# rf_spectrum.net
KiCad netlist of a schematic drawn in EAGLE
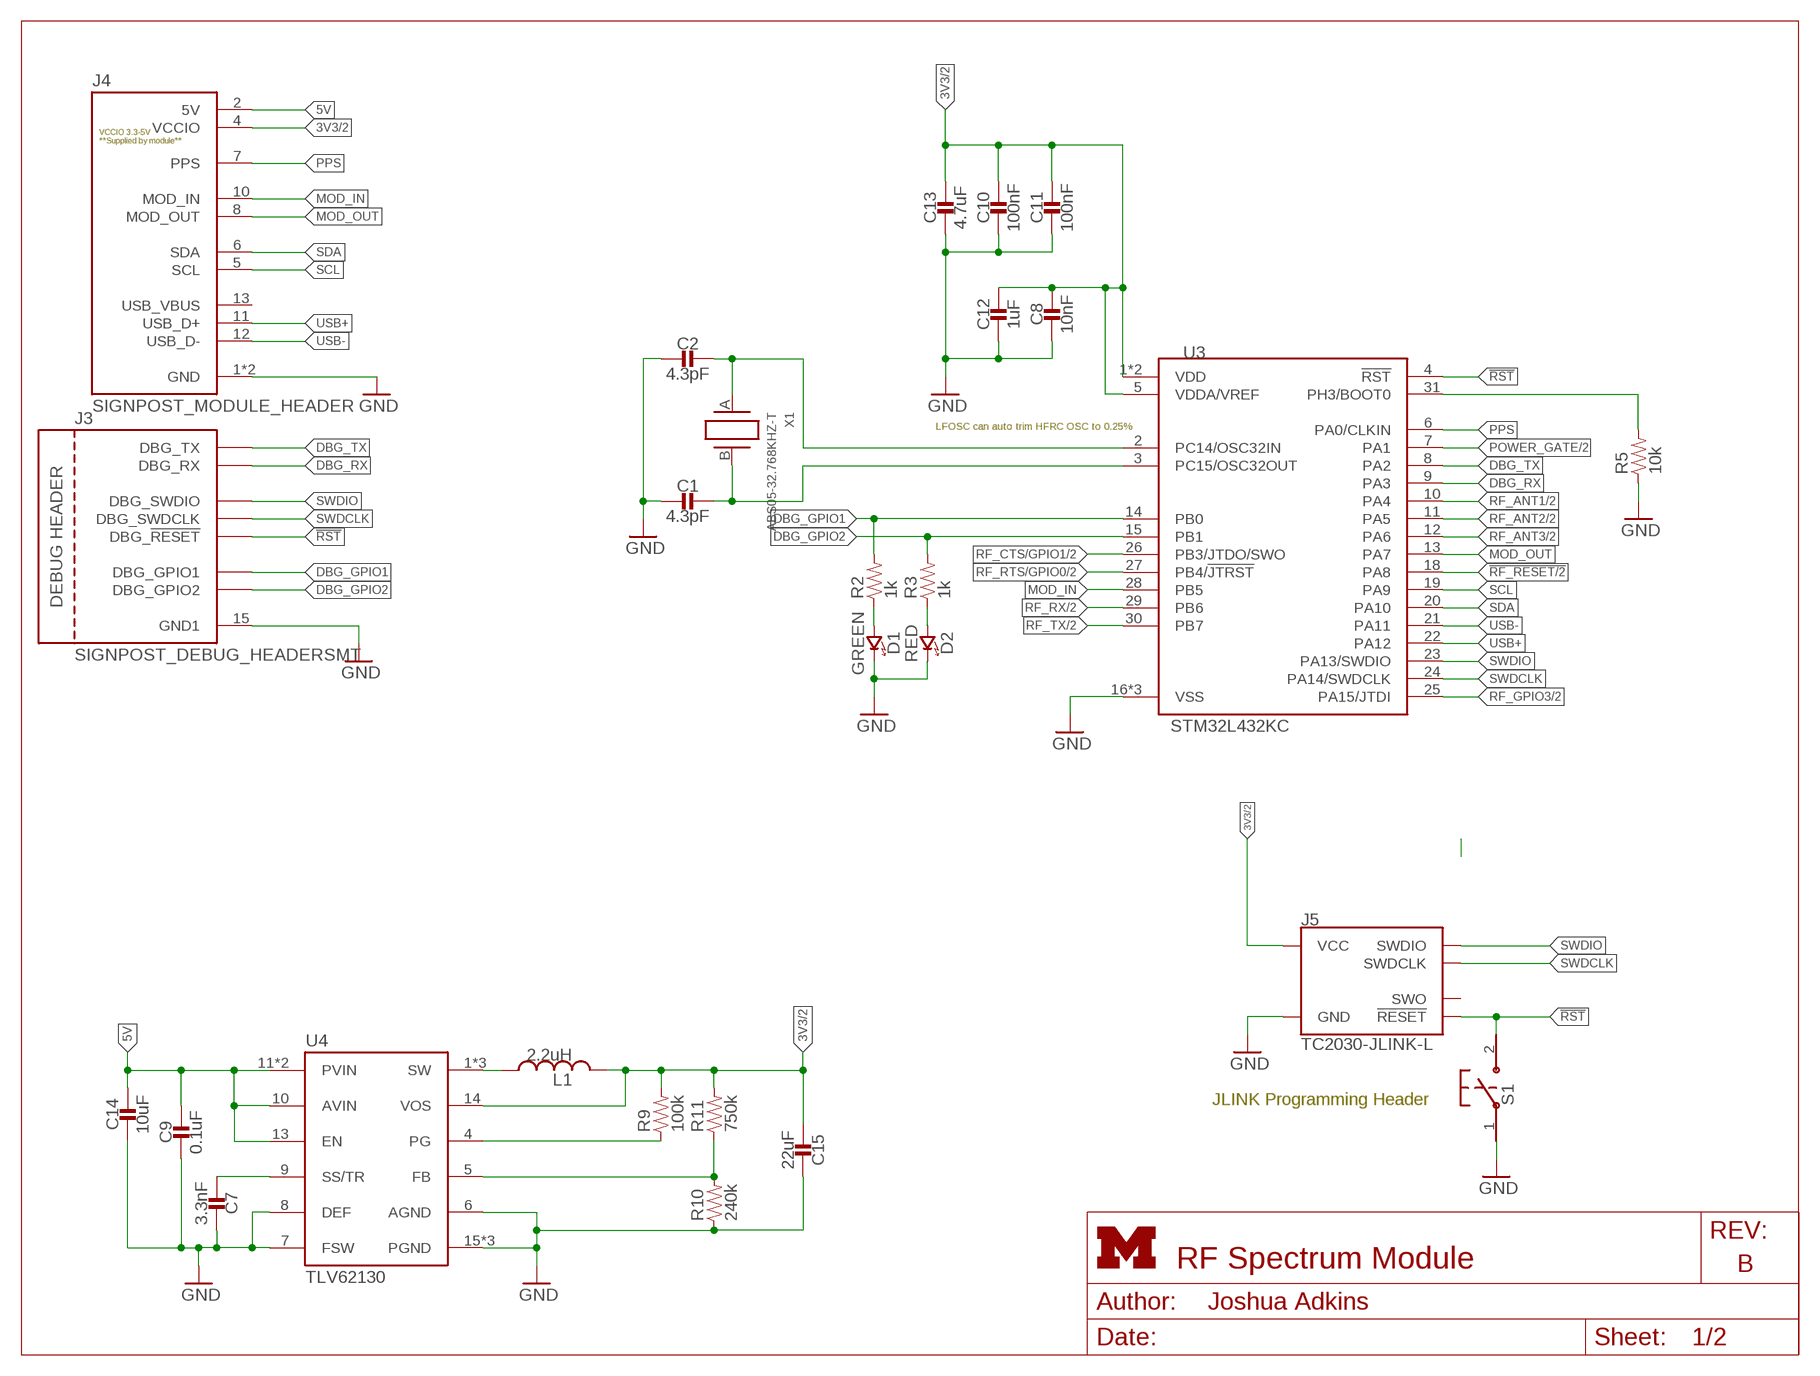
[diagram p0: schematic, sheet 1]
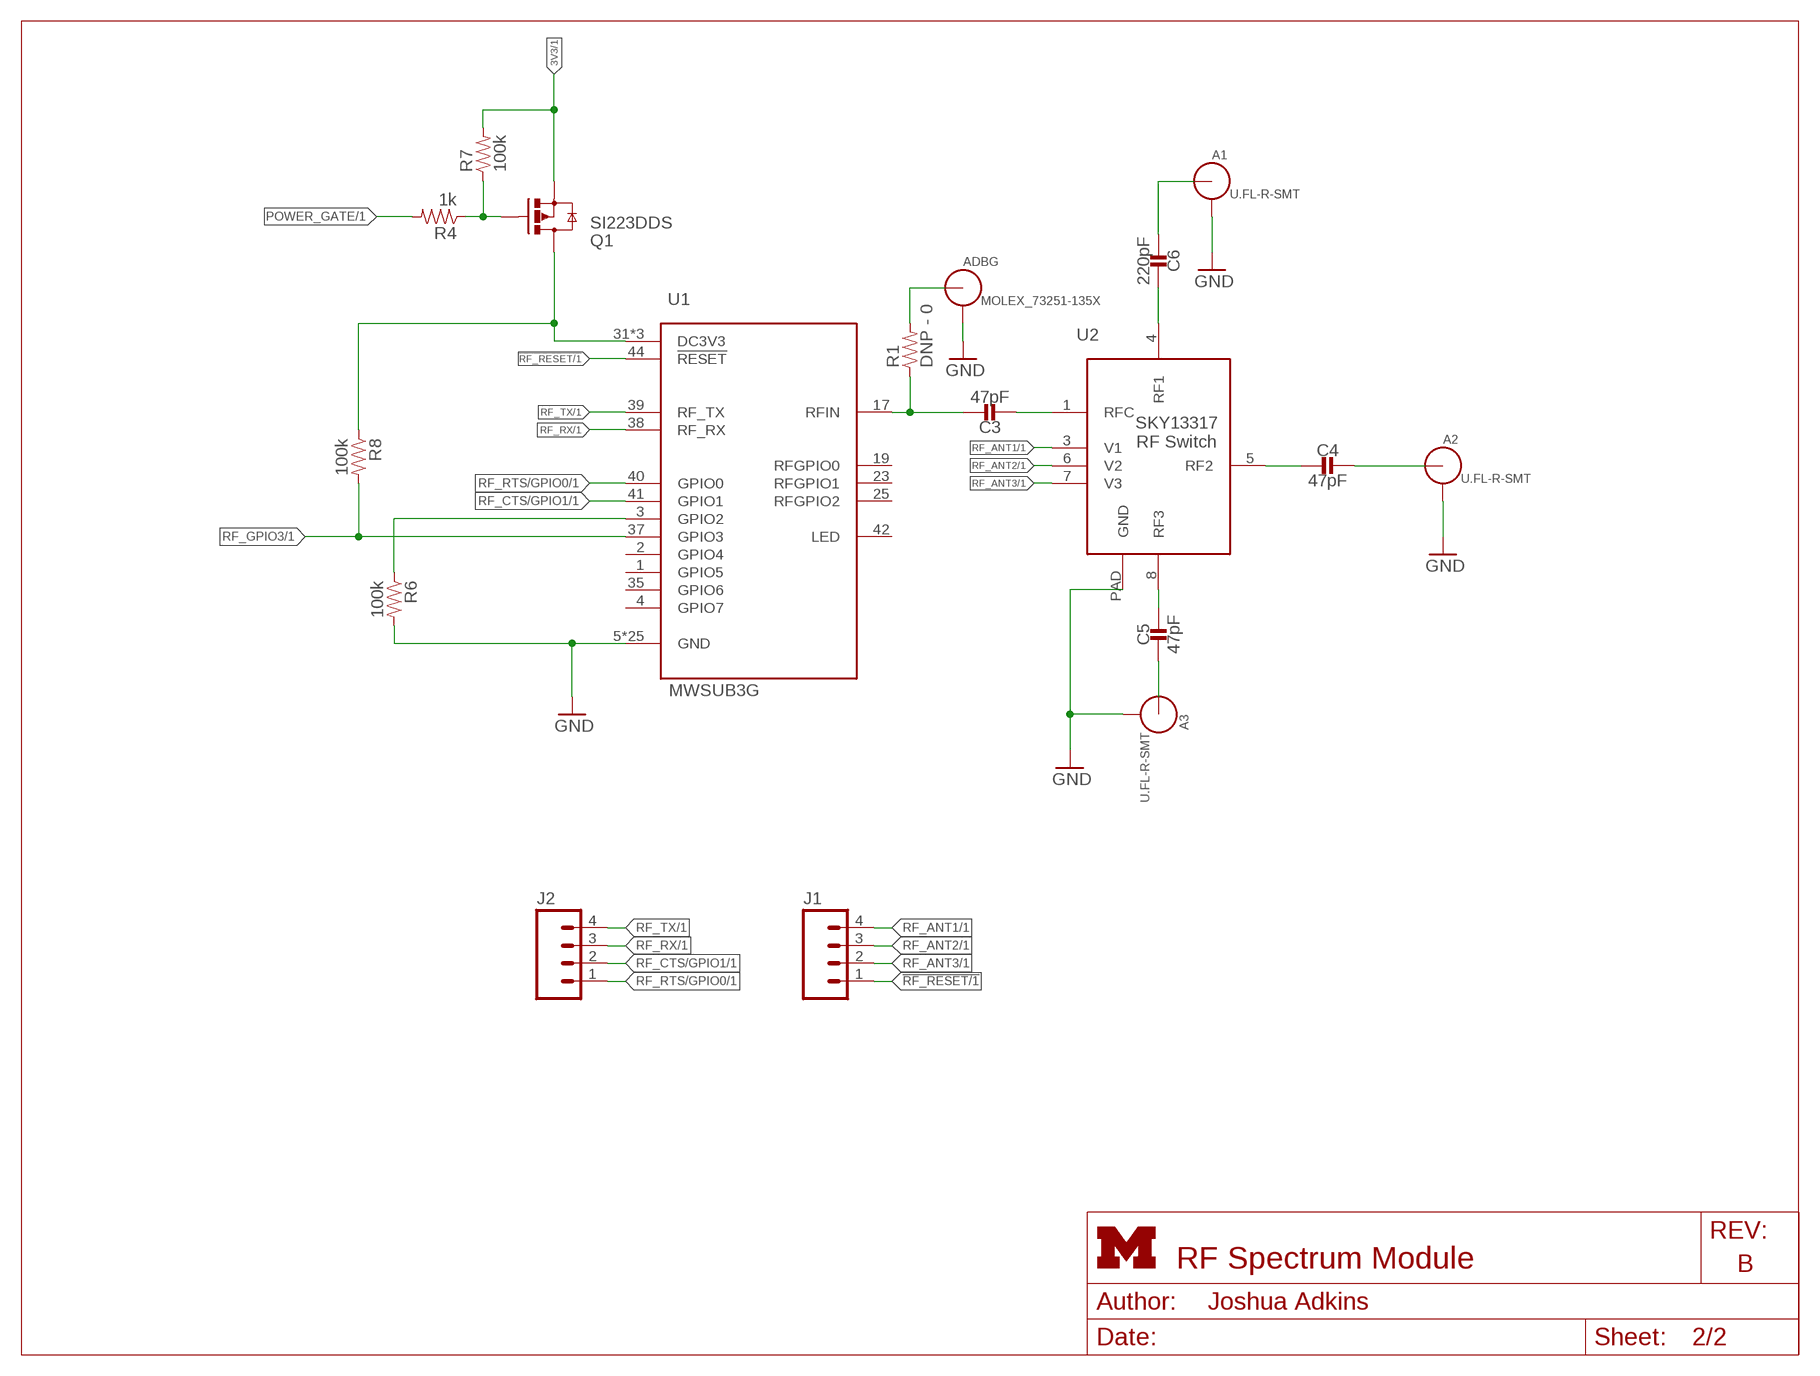
[diagram p1: schematic, sheet 2]

(export (version "E")
  (design (tool "Eeschema 10.0.6"))
  (components
    (comp (ref "C1")
      (value "4.3pF")
      (footprint "eagle-import:0402_CAP")
      (fields (field (name "MANUFACTURER") "Murata") (field (name "MPN") "GRM1555C1H4R3BA01D"))
      (libsource (lib "eagle-import") (part "CAPACITOR0402_CAP"))
    )
    (comp (ref "C2")
      (value "4.3pF")
      (footprint "eagle-import:0402_CAP")
      (fields (field (name "MANUFACTURER") "Murata") (field (name "MPN") "GRM1555C1H4R3BA01D"))
      (libsource (lib "eagle-import") (part "CAPACITOR0402_CAP"))
    )
    (comp (ref "C7")
      (value "3.3nF")
      (footprint "eagle-import:0603_CAP")
      (fields (field (name "MANUFACTURER") "Murata") (field (name "MPN") "GRM188R71H332KA01D"))
      (libsource (lib "eagle-import") (part "CAPACITOR0603_CAP"))
    )
    (comp (ref "C8")
      (value "10nF")
      (footprint "eagle-import:0402_CAP")
      (fields (field (name "MANUFACTURER") "Murata") (field (name "MPN") "GRM155R71H103KA88D"))
      (libsource (lib "eagle-import") (part "CAPACITOR0402_CAP"))
    )
    (comp (ref "C9")
      (value "0.1uF")
      (footprint "eagle-import:0603_CAP")
      (fields (field (name "MANUFACTURER") "Murata") (field (name "MPN") "GRM188R71C104KA01D"))
      (libsource (lib "eagle-import") (part "CAPACITOR0603_CAP"))
    )
    (comp (ref "C10")
      (value "100nF")
      (footprint "eagle-import:0402_CAP")
      (fields (field (name "MANUFACTURER") "Murata") (field (name "MPN") "GRM155R71C104KA88J"))
      (libsource (lib "eagle-import") (part "CAPACITOR0402_CAP"))
    )
    (comp (ref "C11")
      (value "100nF")
      (footprint "eagle-import:0402_CAP")
      (fields (field (name "MANUFACTURER") "Murata") (field (name "MPN") "GRM155R71C104KA88J"))
      (libsource (lib "eagle-import") (part "CAPACITOR0402_CAP"))
    )
    (comp (ref "C12")
      (value "1uF")
      (footprint "eagle-import:0402_CAP")
      (fields (field (name "MANUFACTURER") "Murata") (field (name "MPN") "GRM155R60J105KE19D"))
      (libsource (lib "eagle-import") (part "CAPACITOR0402_CAP"))
    )
    (comp (ref "C13")
      (value "4.7uF")
      (footprint "eagle-import:0402_CAP")
      (fields (field (name "MANUFACTURER") "Murata") (field (name "MPN") "GRM155R60J475ME47D"))
      (libsource (lib "eagle-import") (part "CAPACITOR0402_CAP"))
    )
    (comp (ref "C14")
      (value "10uF")
      (footprint "eagle-import:0603_CAP")
      (fields (field (name "MANUFACTURER") "Murata") (field (name "MPN") "GRM188R60J106ME47J"))
      (libsource (lib "eagle-import") (part "CAPACITOR0603_CAP"))
    )
    (comp (ref "C15")
      (value "22uF")
      (footprint "eagle-import:0603_CAP")
      (fields (field (name "MANUFACTURER") "Murata") (field (name "MPN") "GRM188R60J226MEA0D"))
      (libsource (lib "eagle-import") (part "CAPACITOR0603_CAP"))
    )
    (comp (ref "D1")
      (value "GREEN")
      (footprint "eagle-import:LED-0603")
      (fields (field (name "MANUFACTURER") "Lite-ON") (field (name "MPN") "LTST-C191KGKT"))
      (libsource (lib "eagle-import") (part "LED0603"))
    )
    (comp (ref "D2")
      (value "RED")
      (footprint "eagle-import:LED-0603")
      (fields (field (name "MANUFACTURER") "Lite-On") (field (name "MPN") "LTST-C191KRKT"))
      (libsource (lib "eagle-import") (part "LED0603"))
    )
    (comp (ref "J3")
      (value "SIGNPOST_DEBUG_HEADERSMT")
      (footprint "eagle-import:SIGNPOST_DEBUG_HEADER_SMT")
      (fields (field (name "MANUFACTURER") "Molex") (field (name "MPN") "0015912080"))
      (libsource (lib "eagle-import") (part "SIGNPOST_DEBUG_HEADERSMT"))
    )
    (comp (ref "J4")
      (value "SIGNPOST_MODULE_HEADER")
      (footprint "eagle-import:SIGNPOST_MODULE_HEADER")
      (fields (field (name "MANUFACTURER") "Sullins Connector") (field (name "MPN") "SBH11-PBPC-D07-ST-BK"))
      (libsource (lib "eagle-import") (part "SIGNPOST_MODULE_HEADER"))
    )
    (comp (ref "J5")
      (value "TC2030-JLINK-L")
      (footprint "eagle-import:TC2030-IDC")
      (libsource (lib "eagle-import") (part "TC2030-JLINK-L"))
    )
    (comp (ref "L1")
      (value "2.2uH")
      (footprint "eagle-import:IHL-1212BZ-11")
      (fields (field (name "MANUFACTURER") "Vishay Dale") (field (name "MPN") "IHLP1212BZER2R2M11"))
      (libsource (lib "eagle-import") (part "INDUCTORIHL"))
    )
    (comp (ref "R2")
      (value "1k")
      (footprint "eagle-import:0402_RES")
      (fields (field (name "MANUFACTURER") "Yageo") (field (name "MPN") "RC0402JR-071KL"))
      (libsource (lib "eagle-import") (part "RESISTOR0402_RES"))
    )
    (comp (ref "R3")
      (value "1k")
      (footprint "eagle-import:0402_RES")
      (fields (field (name "MANUFACTURER") "Yageo") (field (name "MPN") "RC0402JR-071KL"))
      (libsource (lib "eagle-import") (part "RESISTOR0402_RES"))
    )
    (comp (ref "R5")
      (value "10k")
      (footprint "eagle-import:0402_RES")
      (fields (field (name "MANUFACTURER") "Yageo") (field (name "MPN") "RC0402JR-071KL"))
      (libsource (lib "eagle-import") (part "RESISTOR0402_RES"))
    )
    (comp (ref "R9")
      (value "100k")
      (footprint "eagle-import:0603-RES")
      (fields (field (name "MANUFACTURER") "Yageo") (field (name "MPN") "RC0603JR-07100KL"))
      (libsource (lib "eagle-import") (part "RESISTOR0603_RES"))
    )
    (comp (ref "R10")
      (value "240k")
      (footprint "eagle-import:0603-RES")
      (fields (field (name "MANUFACTURER") "Yageo") (field (name "MPN") "RC0603JR-07240KL"))
      (libsource (lib "eagle-import") (part "RESISTOR0603_RES"))
    )
    (comp (ref "R11")
      (value "750k")
      (footprint "eagle-import:0603-RES")
      (fields (field (name "MANUFACTURER") "Yageo") (field (name "MPN") "311-750KGRCT-ND"))
      (libsource (lib "eagle-import") (part "RESISTOR0603_RES"))
    )
    (comp (ref "S1")
      (value "B3U-1000P")
      (footprint "eagle-import:B3U-1000P")
      (fields (field (name "MANUFACTURER") "Omron"))
      (libsource (lib "eagle-import") (part "B3U-1000P"))
    )
    (comp (ref "U3")
      (value "STM32L432KC")
      (footprint "eagle-import:UQFN-32")
      (fields (field (name "MANUFACTURER") "STMicroelectronics") (field (name "MPN") "STM32L432KCU6"))
      (libsource (lib "eagle-import") (part "STM32L432KC"))
    )
    (comp (ref "U4")
      (value "TLV62130")
      (footprint "eagle-import:TQFN-16_3MM")
      (fields (field (name "MANUFACTURER") "Texas Instruments") (field (name "MPN") "TLV62130RGTR"))
      (libsource (lib "eagle-import") (part "TLV62130"))
    )
    (comp (ref "X1")
      (value "ABS05-32.768KHZ-T")
      (footprint "eagle-import:ABS05")
      (fields (field (name "MANUFACTURER") "Abracon"))
      (libsource (lib "eagle-import") (part "ABS05-32.768KHZ-T"))
    )
    (comp (ref "A1")
      (value "U.FL-R-SMT")
      (footprint "eagle-import:U.FL_SMT")
      (fields (field (name "MANUFACTURER") "Hirose") (field (name "MPN") "U.FL-R-SMT-1(01)"))
      (libsource (lib "eagle-import") (part "U.FL-R-SMT"))
    )
    (comp (ref "A2")
      (value "U.FL-R-SMT")
      (footprint "eagle-import:U.FL_SMT")
      (fields (field (name "MANUFACTURER") "Hirose") (field (name "MPN") "U.FL-R-SMT-1(01)"))
      (libsource (lib "eagle-import") (part "U.FL-R-SMT"))
    )
    (comp (ref "A3")
      (value "U.FL-R-SMT")
      (footprint "eagle-import:U.FL_SMT")
      (fields (field (name "MANUFACTURER") "Hirose") (field (name "MPN") "U.FL-R-SMT-1(01)"))
      (libsource (lib "eagle-import") (part "U.FL-R-SMT"))
    )
    (comp (ref "ADBG")
      (value "MOLEX_73251-135X")
      (footprint "eagle-import:SMA-J_PCB")
      (fields (field (name "MANUFACTURER") "Molex") (field (name "MPN") "0732511350"))
      (libsource (lib "eagle-import") (part "MOLEX_73251-135X"))
    )
    (comp (ref "C3")
      (value "47pF")
      (footprint "eagle-import:0402_CAP")
      (fields (field (name "MANUFACTURER") "Murata") (field (name "MPN") "GRM1555C1H470FA01D"))
      (libsource (lib "eagle-import") (part "CAPACITOR0402_CAP"))
    )
    (comp (ref "C4")
      (value "47pF")
      (footprint "eagle-import:0402_CAP")
      (fields (field (name "MANUFACTURER") "Murata") (field (name "MPN") "GRM1555C1H470FA01D"))
      (libsource (lib "eagle-import") (part "CAPACITOR0402_CAP"))
    )
    (comp (ref "C5")
      (value "47pF")
      (footprint "eagle-import:0402_CAP")
      (fields (field (name "MANUFACTURER") "Murata") (field (name "MPN") "GRM1555C1H470FA01D"))
      (libsource (lib "eagle-import") (part "CAPACITOR0402_CAP"))
    )
    (comp (ref "C6")
      (value "220pF")
      (footprint "eagle-import:0402_CAP")
      (fields (field (name "MANUFACTURER") "Murata") (field (name "MPN") "GRM1555C1H221JA01D"))
      (libsource (lib "eagle-import") (part "CAPACITOR0402_CAP"))
    )
    (comp (ref "J1")
      (value "M04PTH")
      (footprint "eagle-import:1X04")
      (fields (field (name "MANUFACTURER") "Molex") (field (name "MPN") "0901200764"))
      (libsource (lib "eagle-import") (part "M04PTH"))
    )
    (comp (ref "J2")
      (value "M04PTH")
      (footprint "eagle-import:1X04")
      (fields (field (name "MANUFACTURER") "Molex") (field (name "MPN") "0901200764"))
      (libsource (lib "eagle-import") (part "M04PTH"))
    )
    (comp (ref "Q1")
      (value "SI223DDS")
      (footprint "eagle-import:SOT23-3")
      (fields (field (name "MANUFACTURER") "Vishay Siliconix") (field (name "MPN") "SI2333DDS-T1-GE3"))
      (libsource (lib "eagle-import") (part "SI223DDS"))
    )
    (comp (ref "R1")
      (value "DNP - 0")
      (footprint "eagle-import:0402_RES")
      (fields (field (name "MANUFACTURER") "Yageo") (field (name "MPN") "RC0402JR-070RL"))
      (libsource (lib "eagle-import") (part "RESISTOR0402_RES"))
    )
    (comp (ref "R4")
      (value "1k")
      (footprint "eagle-import:0402_RES")
      (fields (field (name "MANUFACTURER") "Yageo") (field (name "MPN") "RC0402JR-071KL"))
      (libsource (lib "eagle-import") (part "RESISTOR0402_RES"))
    )
    (comp (ref "R6")
      (value "100k")
      (footprint "eagle-import:0402_RES")
      (fields (field (name "MANUFACTURER") "Yageo") (field (name "MPN") "RC0402FR-07100KL"))
      (libsource (lib "eagle-import") (part "RESISTOR0402_RES"))
    )
    (comp (ref "R7")
      (value "100k")
      (footprint "eagle-import:0402_RES")
      (fields (field (name "MANUFACTURER") "Yageo") (field (name "MPN") "RC0402FR-07100KL"))
      (libsource (lib "eagle-import") (part "RESISTOR0402_RES"))
    )
    (comp (ref "R8")
      (value "100k")
      (footprint "eagle-import:0402_RES")
      (fields (field (name "MANUFACTURER") "Yageo") (field (name "MPN") "RC0402FR-07100KL"))
      (libsource (lib "eagle-import") (part "RESISTOR0402_RES"))
    )
    (comp (ref "U1")
      (value "MWSUB3G")
      (footprint "eagle-import:MWSUB3G")
      (fields (field (name "MANUFACTURER") "RFExplorer"))
      (libsource (lib "eagle-import") (part "MWSUB3G"))
    )
    (comp (ref "U2")
      (value "SKY13317")
      (footprint "eagle-import:XDFN-8")
      (fields (field (name "MANUFACTURER") "Skworks Solutions") (field (name "MPN") "SKY13317-373LF"))
      (libsource (lib "eagle-import") (part "SKY13317"))
    )
  )
  (nets
    (net (code "1") (name "3V3") (class "Default")
      (node (ref "C10") (pin "1") (pinfunction "1_1") (pintype "bidirectional"))
      (node (ref "C11") (pin "1") (pinfunction "1_1") (pintype "bidirectional"))
      (node (ref "C12") (pin "1") (pinfunction "1_1") (pintype "bidirectional"))
      (node (ref "C13") (pin "1") (pinfunction "1_1") (pintype "bidirectional"))
      (node (ref "C15") (pin "2") (pinfunction "2_2") (pintype "bidirectional"))
      (node (ref "C8") (pin "1") (pinfunction "1_1") (pintype "bidirectional"))
      (node (ref "J4") (pin "4") (pinfunction "VCCIO_4") (pintype "bidirectional"))
      (node (ref "J5") (pin "1") (pinfunction "VCC_1") (pintype "bidirectional"))
      (node (ref "L1") (pin "P$2") (pinfunction "2_P$2") (pintype "bidirectional"))
      (node (ref "Q1") (pin "2") (pinfunction "S_2") (pintype "passive"))
      (node (ref "R11") (pin "2") (pinfunction "2_2") (pintype "passive"))
      (node (ref "R7") (pin "2") (pinfunction "2_2") (pintype "passive"))
      (node (ref "R9") (pin "2") (pinfunction "2_2") (pintype "passive"))
      (node (ref "U3") (pin "1") (pinfunction "VDD_1") (pintype "bidirectional"))
      (node (ref "U3") (pin "17") (pinfunction "VDD_17") (pintype "bidirectional"))
      (node (ref "U3") (pin "5") (pinfunction "VDDA/VREF_5") (pintype "bidirectional"))
      (node (ref "U4") (pin "14") (pinfunction "VOS_14") (pintype "bidirectional"))
    )
    (net (code "2") (name "5V") (class "Default")
      (node (ref "C14") (pin "1") (pinfunction "1_1") (pintype "bidirectional"))
      (node (ref "C9") (pin "1") (pinfunction "1_1") (pintype "bidirectional"))
      (node (ref "J4") (pin "2") (pinfunction "5V_2") (pintype "bidirectional"))
      (node (ref "U4") (pin "10") (pinfunction "AVIN_10") (pintype "bidirectional"))
      (node (ref "U4") (pin "11") (pinfunction "PVIN_11") (pintype "bidirectional"))
      (node (ref "U4") (pin "12") (pinfunction "PVIN_12") (pintype "bidirectional"))
      (node (ref "U4") (pin "13") (pinfunction "EN_13") (pintype "bidirectional"))
    )
    (net (code "3") (name "DBG_GPIO1") (class "Default")
      (node (ref "J3") (pin "16") (pinfunction "DBG_GPIO1_16") (pintype "bidirectional"))
      (node (ref "R2") (pin "2") (pinfunction "2_2") (pintype "passive"))
      (node (ref "U3") (pin "14") (pinfunction "PB0_14") (pintype "bidirectional"))
    )
    (net (code "4") (name "DBG_GPIO2") (class "Default")
      (node (ref "J3") (pin "19") (pinfunction "DBG_GPIO2_19") (pintype "bidirectional"))
      (node (ref "R3") (pin "2") (pinfunction "2_2") (pintype "passive"))
      (node (ref "U3") (pin "15") (pinfunction "PB1_15") (pintype "bidirectional"))
    )
    (net (code "5") (name "DBG_RX") (class "Default")
      (node (ref "J3") (pin "18") (pinfunction "DBG_RX_18") (pintype "bidirectional"))
      (node (ref "U3") (pin "9") (pinfunction "PA3_9") (pintype "bidirectional"))
    )
    (net (code "6") (name "DBG_TX") (class "Default")
      (node (ref "J3") (pin "17") (pinfunction "DBG_TX_17") (pintype "bidirectional"))
      (node (ref "U3") (pin "8") (pinfunction "PA2_8") (pintype "bidirectional"))
    )
    (net (code "7") (name "GND") (class "Default")
      (node (ref "A1") (pin "GND1") (pinfunction "P$2_GND1") (pintype "bidirectional"))
      (node (ref "A1") (pin "GND2") (pinfunction "P$2_GND2") (pintype "bidirectional"))
      (node (ref "A2") (pin "GND1") (pinfunction "P$2_GND1") (pintype "bidirectional"))
      (node (ref "A2") (pin "GND2") (pinfunction "P$2_GND2") (pintype "bidirectional"))
      (node (ref "A3") (pin "GND1") (pinfunction "P$2_GND1") (pintype "bidirectional"))
      (node (ref "A3") (pin "GND2") (pinfunction "P$2_GND2") (pintype "bidirectional"))
      (node (ref "ADBG") (pin "2") (pinfunction "P$2_2") (pintype "bidirectional"))
      (node (ref "ADBG") (pin "3") (pinfunction "P$2_3") (pintype "bidirectional"))
      (node (ref "ADBG") (pin "4") (pinfunction "P$2_4") (pintype "bidirectional"))
      (node (ref "ADBG") (pin "5") (pinfunction "P$2_5") (pintype "bidirectional"))
      (node (ref "C1") (pin "2") (pinfunction "2_2") (pintype "bidirectional"))
      (node (ref "C10") (pin "2") (pinfunction "2_2") (pintype "bidirectional"))
      (node (ref "C11") (pin "2") (pinfunction "2_2") (pintype "bidirectional"))
      (node (ref "C12") (pin "2") (pinfunction "2_2") (pintype "bidirectional"))
      (node (ref "C13") (pin "2") (pinfunction "2_2") (pintype "bidirectional"))
      (node (ref "C14") (pin "2") (pinfunction "2_2") (pintype "bidirectional"))
      (node (ref "C15") (pin "1") (pinfunction "1_1") (pintype "bidirectional"))
      (node (ref "C2") (pin "2") (pinfunction "2_2") (pintype "bidirectional"))
      (node (ref "C7") (pin "1") (pinfunction "1_1") (pintype "bidirectional"))
      (node (ref "C8") (pin "2") (pinfunction "2_2") (pintype "bidirectional"))
      (node (ref "C9") (pin "2") (pinfunction "2_2") (pintype "bidirectional"))
      (node (ref "D1") (pin "C") (pinfunction "CATHODE_C") (pintype "bidirectional"))
      (node (ref "D2") (pin "C") (pinfunction "CATHODE_C") (pintype "bidirectional"))
      (node (ref "J3") (pin "15") (pinfunction "GND1_15") (pintype "bidirectional"))
      (node (ref "J4") (pin "1") (pinfunction "GND_1") (pintype "bidirectional"))
      (node (ref "J4") (pin "14") (pinfunction "GND_14") (pintype "bidirectional"))
      (node (ref "J5") (pin "5") (pinfunction "GND_5") (pintype "bidirectional"))
      (node (ref "R10") (pin "1") (pinfunction "1_1") (pintype "passive"))
      (node (ref "R5") (pin "1") (pinfunction "1_1") (pintype "passive"))
      (node (ref "R6") (pin "2") (pinfunction "2_2") (pintype "passive"))
      (node (ref "S1") (pin "1") (pinfunction "P$1_1") (pintype "passive"))
      (node (ref "U1") (pin "10") (pinfunction "GND_10") (pintype "bidirectional"))
      (node (ref "U1") (pin "11") (pinfunction "GND_11") (pintype "bidirectional"))
      (node (ref "U1") (pin "12") (pinfunction "GND_12") (pintype "bidirectional"))
      (node (ref "U1") (pin "13") (pinfunction "GND_13") (pintype "bidirectional"))
      (node (ref "U1") (pin "14") (pinfunction "GND_14") (pintype "bidirectional"))
      (node (ref "U1") (pin "15") (pinfunction "GND_15") (pintype "bidirectional"))
      (node (ref "U1") (pin "16") (pinfunction "GND_16") (pintype "bidirectional"))
      (node (ref "U1") (pin "18") (pinfunction "GND_18") (pintype "bidirectional"))
      (node (ref "U1") (pin "20") (pinfunction "GND_20") (pintype "bidirectional"))
      (node (ref "U1") (pin "21") (pinfunction "GND_21") (pintype "bidirectional"))
      (node (ref "U1") (pin "22") (pinfunction "GND_22") (pintype "bidirectional"))
      (node (ref "U1") (pin "24") (pinfunction "GND_24") (pintype "bidirectional"))
      (node (ref "U1") (pin "26") (pinfunction "GND_26") (pintype "bidirectional"))
      (node (ref "U1") (pin "27") (pinfunction "GND_27") (pintype "bidirectional"))
      (node (ref "U1") (pin "28") (pinfunction "GND_28") (pintype "bidirectional"))
      (node (ref "U1") (pin "29") (pinfunction "GND_29") (pintype "bidirectional"))
      (node (ref "U1") (pin "34") (pinfunction "GND_34") (pintype "bidirectional"))
      (node (ref "U1") (pin "43") (pinfunction "GND_43") (pintype "bidirectional"))
      (node (ref "U1") (pin "45") (pinfunction "GND_45") (pintype "bidirectional"))
      (node (ref "U1") (pin "46") (pinfunction "GND_46") (pintype "bidirectional"))
      (node (ref "U1") (pin "5") (pinfunction "GND_5") (pintype "bidirectional"))
      (node (ref "U1") (pin "6") (pinfunction "GND_6") (pintype "bidirectional"))
      (node (ref "U1") (pin "7") (pinfunction "GND_7") (pintype "bidirectional"))
      (node (ref "U1") (pin "8") (pinfunction "GND_8") (pintype "bidirectional"))
      (node (ref "U1") (pin "9") (pinfunction "GND_9") (pintype "bidirectional"))
      (node (ref "U2") (pin "PAD") (pinfunction "GND_PAD") (pintype "bidirectional"))
      (node (ref "U3") (pin "16") (pinfunction "VSS_16") (pintype "bidirectional"))
      (node (ref "U3") (pin "32") (pinfunction "VSS_32") (pintype "bidirectional"))
      (node (ref "U3") (pin "THERMAL") (pinfunction "VSS_THERMAL") (pintype "bidirectional"))
      (node (ref "U4") (pin "15") (pinfunction "PGND_15") (pintype "bidirectional"))
      (node (ref "U4") (pin "16") (pinfunction "PGND_16") (pintype "bidirectional"))
      (node (ref "U4") (pin "6") (pinfunction "AGND_6") (pintype "bidirectional"))
      (node (ref "U4") (pin "7") (pinfunction "FSW_7") (pintype "bidirectional"))
      (node (ref "U4") (pin "8") (pinfunction "DEF_8") (pintype "bidirectional"))
      (node (ref "U4") (pin "GND") (pinfunction "PGND_GND") (pintype "bidirectional"))
    )
    (net (code "8") (name "MOD_IN") (class "Default")
      (node (ref "J4") (pin "10") (pinfunction "MOD_IN_10") (pintype "bidirectional"))
      (node (ref "U3") (pin "28") (pinfunction "PB5_28") (pintype "bidirectional"))
    )
    (net (code "9") (name "MOD_OUT") (class "Default")
      (node (ref "J4") (pin "8") (pinfunction "MOD_OUT_8") (pintype "bidirectional"))
      (node (ref "U3") (pin "13") (pinfunction "PA7_13") (pintype "bidirectional"))
    )
    (net (code "10") (name "Net-(A1-ANT)") (class "Default")
      (node (ref "A1") (pin "SIG") (pinfunction "ANT_SIG") (pintype "bidirectional"))
      (node (ref "C6") (pin "2") (pinfunction "2_2") (pintype "bidirectional"))
    )
    (net (code "11") (name "Net-(A2-ANT)") (class "Default")
      (node (ref "A2") (pin "SIG") (pinfunction "ANT_SIG") (pintype "bidirectional"))
      (node (ref "C4") (pin "1") (pinfunction "1_1") (pintype "bidirectional"))
    )
    (net (code "12") (name "Net-(A3-ANT)") (class "Default")
      (node (ref "A3") (pin "SIG") (pinfunction "ANT_SIG") (pintype "bidirectional"))
      (node (ref "C5") (pin "2") (pinfunction "2_2") (pintype "bidirectional"))
    )
    (net (code "13") (name "Net-(ADBG-ANT)") (class "Default")
      (node (ref "ADBG") (pin "1") (pinfunction "ANT_1") (pintype "bidirectional"))
      (node (ref "R1") (pin "2") (pinfunction "2_2") (pintype "passive"))
    )
    (net (code "14") (name "Net-(D1-ANODE)") (class "Default")
      (node (ref "D1") (pin "A") (pinfunction "ANODE_A") (pintype "bidirectional"))
      (node (ref "R2") (pin "1") (pinfunction "1_1") (pintype "passive"))
    )
    (net (code "15") (name "Net-(D2-ANODE)") (class "Default")
      (node (ref "D2") (pin "A") (pinfunction "ANODE_A") (pintype "bidirectional"))
      (node (ref "R3") (pin "1") (pinfunction "1_1") (pintype "passive"))
    )
    (net (code "16") (name "Net-(L1-1)") (class "Default")
      (node (ref "L1") (pin "P$1") (pinfunction "1_P$1") (pintype "bidirectional"))
      (node (ref "U4") (pin "1") (pinfunction "SW_1") (pintype "bidirectional"))
      (node (ref "U4") (pin "2") (pinfunction "SW_2") (pintype "bidirectional"))
      (node (ref "U4") (pin "3") (pinfunction "SW_3") (pintype "bidirectional"))
    )
    (net (code "17") (name "Net-(Q1-D)") (class "Default")
      (node (ref "Q1") (pin "3") (pinfunction "D_3") (pintype "passive"))
      (node (ref "R8") (pin "1") (pinfunction "1_1") (pintype "passive"))
      (node (ref "U1") (pin "31") (pinfunction "DC3V3_31") (pintype "bidirectional"))
      (node (ref "U1") (pin "32") (pinfunction "DC3V3_32") (pintype "bidirectional"))
      (node (ref "U1") (pin "33") (pinfunction "DC3V3_33") (pintype "bidirectional"))
    )
    (net (code "18") (name "Net-(Q1-G)") (class "Default")
      (node (ref "Q1") (pin "1") (pinfunction "G_1") (pintype "passive"))
      (node (ref "R4") (pin "1") (pinfunction "1_1") (pintype "passive"))
      (node (ref "R7") (pin "1") (pinfunction "1_1") (pintype "passive"))
    )
    (net (code "19") (name "Net-(U1-GPIO2)") (class "Default")
      (node (ref "R6") (pin "1") (pinfunction "1_1") (pintype "passive"))
      (node (ref "U1") (pin "3") (pinfunction "GPIO2_3") (pintype "bidirectional"))
    )
    (net (code "20") (name "Net-(U1-RFIN)") (class "Default")
      (node (ref "C3") (pin "1") (pinfunction "1_1") (pintype "bidirectional"))
      (node (ref "R1") (pin "1") (pinfunction "1_1") (pintype "passive"))
      (node (ref "U1") (pin "17") (pinfunction "RFIN_17") (pintype "bidirectional"))
    )
    (net (code "21") (name "Net-(U2-RF1)") (class "Default")
      (node (ref "C6") (pin "1") (pinfunction "1_1") (pintype "bidirectional"))
      (node (ref "U2") (pin "4") (pinfunction "RF1_4") (pintype "bidirectional"))
    )
    (net (code "22") (name "Net-(U2-RF2)") (class "Default")
      (node (ref "C4") (pin "2") (pinfunction "2_2") (pintype "bidirectional"))
      (node (ref "U2") (pin "5") (pinfunction "RF2_5") (pintype "bidirectional"))
    )
    (net (code "23") (name "Net-(U2-RF3)") (class "Default")
      (node (ref "C5") (pin "1") (pinfunction "1_1") (pintype "bidirectional"))
      (node (ref "U2") (pin "8") (pinfunction "RF3_8") (pintype "bidirectional"))
    )
    (net (code "24") (name "Net-(U2-RFC)") (class "Default")
      (node (ref "C3") (pin "2") (pinfunction "2_2") (pintype "bidirectional"))
      (node (ref "U2") (pin "1") (pinfunction "RFC_1") (pintype "bidirectional"))
    )
    (net (code "25") (name "Net-(U3-PC14{slash}OSC32IN)") (class "Default")
      (node (ref "C2") (pin "1") (pinfunction "1_1") (pintype "bidirectional"))
      (node (ref "U3") (pin "2") (pinfunction "PC14/OSC32IN_2") (pintype "bidirectional"))
      (node (ref "X1") (pin "A") (pinfunction "1_A") (pintype "bidirectional"))
    )
    (net (code "26") (name "Net-(U3-PC15{slash}OSC32OUT)") (class "Default")
      (node (ref "C1") (pin "1") (pinfunction "1_1") (pintype "bidirectional"))
      (node (ref "U3") (pin "3") (pinfunction "PC15/OSC32OUT_3") (pintype "bidirectional"))
      (node (ref "X1") (pin "B") (pinfunction "2_B") (pintype "bidirectional"))
    )
    (net (code "27") (name "Net-(U3-PH3{slash}BOOT0)") (class "Default")
      (node (ref "R5") (pin "2") (pinfunction "2_2") (pintype "passive"))
      (node (ref "U3") (pin "31") (pinfunction "PH3/BOOT0_31") (pintype "bidirectional"))
    )
    (net (code "28") (name "Net-(U4-FB)") (class "Default")
      (node (ref "R10") (pin "2") (pinfunction "2_2") (pintype "passive"))
      (node (ref "R11") (pin "1") (pinfunction "1_1") (pintype "passive"))
      (node (ref "U4") (pin "5") (pinfunction "FB_5") (pintype "bidirectional"))
    )
    (net (code "29") (name "Net-(U4-PG)") (class "Default")
      (node (ref "R9") (pin "1") (pinfunction "1_1") (pintype "passive"))
      (node (ref "U4") (pin "4") (pinfunction "PG_4") (pintype "bidirectional"))
    )
    (net (code "30") (name "Net-(U4-SS{slash}TR)") (class "Default")
      (node (ref "C7") (pin "2") (pinfunction "2_2") (pintype "bidirectional"))
      (node (ref "U4") (pin "9") (pinfunction "SS/TR_9") (pintype "bidirectional"))
    )
    (net (code "31") (name "POWER_GATE") (class "Default")
      (node (ref "R4") (pin "2") (pinfunction "2_2") (pintype "passive"))
      (node (ref "U3") (pin "7") (pinfunction "PA1_7") (pintype "bidirectional"))
    )
    (net (code "32") (name "PPS") (class "Default")
      (node (ref "J4") (pin "7") (pinfunction "PPS_7") (pintype "bidirectional"))
      (node (ref "U3") (pin "6") (pinfunction "PA0/CLKIN_6") (pintype "bidirectional"))
    )
    (net (code "33") (name "RF_ANT1") (class "Default")
      (node (ref "J1") (pin "4") (pinfunction "4_4") (pintype "passive"))
      (node (ref "U2") (pin "3") (pinfunction "V1_3") (pintype "bidirectional"))
      (node (ref "U3") (pin "10") (pinfunction "PA4_10") (pintype "bidirectional"))
    )
    (net (code "34") (name "RF_ANT2") (class "Default")
      (node (ref "J1") (pin "3") (pinfunction "3_3") (pintype "passive"))
      (node (ref "U2") (pin "6") (pinfunction "V2_6") (pintype "bidirectional"))
      (node (ref "U3") (pin "11") (pinfunction "PA5_11") (pintype "bidirectional"))
    )
    (net (code "35") (name "RF_ANT3") (class "Default")
      (node (ref "J1") (pin "2") (pinfunction "2_2") (pintype "passive"))
      (node (ref "U2") (pin "7") (pinfunction "V3_7") (pintype "bidirectional"))
      (node (ref "U3") (pin "12") (pinfunction "PA6_12") (pintype "bidirectional"))
    )
    (net (code "36") (name "RF_CTS{slash}GPIO1") (class "Default")
      (node (ref "J2") (pin "2") (pinfunction "2_2") (pintype "passive"))
      (node (ref "U1") (pin "41") (pinfunction "GPIO1_41") (pintype "bidirectional"))
      (node (ref "U3") (pin "26") (pinfunction "PB3/JTDO/SWO_26") (pintype "bidirectional"))
    )
    (net (code "37") (name "RF_GPIO3") (class "Default")
      (node (ref "R8") (pin "2") (pinfunction "2_2") (pintype "passive"))
      (node (ref "U1") (pin "37") (pinfunction "GPIO3_37") (pintype "bidirectional"))
      (node (ref "U3") (pin "25") (pinfunction "PA15/JTDI_25") (pintype "bidirectional"))
    )
    (net (code "38") (name "RF_RTS{slash}GPIO0") (class "Default")
      (node (ref "J2") (pin "1") (pinfunction "1_1") (pintype "passive"))
      (node (ref "U1") (pin "40") (pinfunction "GPIO0_40") (pintype "bidirectional"))
      (node (ref "U3") (pin "27") (pinfunction "PB4/~{JTRST}_27") (pintype "bidirectional"))
    )
    (net (code "39") (name "RF_RX") (class "Default")
      (node (ref "J2") (pin "3") (pinfunction "3_3") (pintype "passive"))
      (node (ref "U1") (pin "38") (pinfunction "RF_RX_38") (pintype "bidirectional"))
      (node (ref "U3") (pin "29") (pinfunction "PB6_29") (pintype "bidirectional"))
    )
    (net (code "40") (name "RF_TX") (class "Default")
      (node (ref "J2") (pin "4") (pinfunction "4_4") (pintype "passive"))
      (node (ref "U1") (pin "39") (pinfunction "RF_TX_39") (pintype "bidirectional"))
      (node (ref "U3") (pin "30") (pinfunction "PB7_30") (pintype "bidirectional"))
    )
    (net (code "41") (name "SCL") (class "Default")
      (node (ref "J4") (pin "5") (pinfunction "SCL_5") (pintype "bidirectional"))
      (node (ref "U3") (pin "19") (pinfunction "PA9_19") (pintype "bidirectional"))
    )
    (net (code "42") (name "SDA") (class "Default")
      (node (ref "J4") (pin "6") (pinfunction "SDA_6") (pintype "bidirectional"))
      (node (ref "U3") (pin "20") (pinfunction "PA10_20") (pintype "bidirectional"))
    )
    (net (code "43") (name "SWDCLK") (class "Default")
      (node (ref "J3") (pin "21") (pinfunction "DBG_SWDCLK_21") (pintype "bidirectional"))
      (node (ref "J5") (pin "4") (pinfunction "SWDCLK_4") (pintype "bidirectional"))
      (node (ref "U3") (pin "24") (pinfunction "PA14/SWDCLK_24") (pintype "bidirectional"))
    )
    (net (code "44") (name "SWDIO") (class "Default")
      (node (ref "J3") (pin "22") (pinfunction "DBG_SWDIO_22") (pintype "bidirectional"))
      (node (ref "J5") (pin "2") (pinfunction "SWDIO_2") (pintype "bidirectional"))
      (node (ref "U3") (pin "23") (pinfunction "PA13/SWDIO_23") (pintype "bidirectional"))
    )
    (net (code "45") (name "USB+") (class "Default")
      (node (ref "J4") (pin "11") (pinfunction "USB_D+_11") (pintype "bidirectional"))
      (node (ref "U3") (pin "22") (pinfunction "PA12_22") (pintype "bidirectional"))
    )
    (net (code "46") (name "USB-") (class "Default")
      (node (ref "J4") (pin "12") (pinfunction "USB_D-_12") (pintype "bidirectional"))
      (node (ref "U3") (pin "21") (pinfunction "PA11_21") (pintype "bidirectional"))
    )
    (net (code "47") (name "unconnected-(J4-USB_VBUS-Pad13)") (class "Default")
      (node (ref "J4") (pin "13") (pinfunction "USB_VBUS_13") (pintype "bidirectional"))
    )
    (net (code "48") (name "unconnected-(J5-SWO-Pad6)") (class "Default")
      (node (ref "J5") (pin "6") (pinfunction "SWO_6") (pintype "bidirectional"))
    )
    (net (code "49") (name "unconnected-(U1-GPIO4-Pad2)") (class "Default")
      (node (ref "U1") (pin "2") (pinfunction "GPIO4_2") (pintype "bidirectional"))
    )
    (net (code "50") (name "unconnected-(U1-GPIO5-Pad1)") (class "Default")
      (node (ref "U1") (pin "1") (pinfunction "GPIO5_1") (pintype "bidirectional"))
    )
    (net (code "51") (name "unconnected-(U1-GPIO6-Pad35)") (class "Default")
      (node (ref "U1") (pin "35") (pinfunction "GPIO6_35") (pintype "bidirectional"))
    )
    (net (code "52") (name "unconnected-(U1-GPIO7-Pad4)") (class "Default")
      (node (ref "U1") (pin "4") (pinfunction "GPIO7_4") (pintype "bidirectional"))
    )
    (net (code "53") (name "unconnected-(U1-LED-Pad42)") (class "Default")
      (node (ref "U1") (pin "42") (pinfunction "LED_42") (pintype "bidirectional"))
    )
    (net (code "54") (name "unconnected-(U1-RFGPIO0-Pad19)") (class "Default")
      (node (ref "U1") (pin "19") (pinfunction "RFGPIO0_19") (pintype "bidirectional"))
    )
    (net (code "55") (name "unconnected-(U1-RFGPIO1-Pad23)") (class "Default")
      (node (ref "U1") (pin "23") (pinfunction "RFGPIO1_23") (pintype "bidirectional"))
    )
    (net (code "56") (name "unconnected-(U1-RFGPIO2-Pad25)") (class "Default")
      (node (ref "U1") (pin "25") (pinfunction "RFGPIO2_25") (pintype "bidirectional"))
    )
    (net (code "57") (name "~{RF_RESET}") (class "Default")
      (node (ref "J1") (pin "1") (pinfunction "1_1") (pintype "passive"))
      (node (ref "U1") (pin "44") (pinfunction "~{RESET}_44") (pintype "bidirectional"))
      (node (ref "U3") (pin "18") (pinfunction "PA8_18") (pintype "bidirectional"))
    )
    (net (code "58") (name "~{RST}") (class "Default")
      (node (ref "J3") (pin "20") (pinfunction "DBG_~{RESET}_20") (pintype "bidirectional"))
      (node (ref "J5") (pin "3") (pinfunction "~{RESET}_3") (pintype "bidirectional"))
      (node (ref "S1") (pin "2") (pinfunction "P$2_2") (pintype "passive"))
      (node (ref "U3") (pin "4") (pinfunction "~{RST}_4") (pintype "bidirectional"))
    )
  )
)
